# Boardd.net
KiCad netlist of a schematic drawn in EAGLE
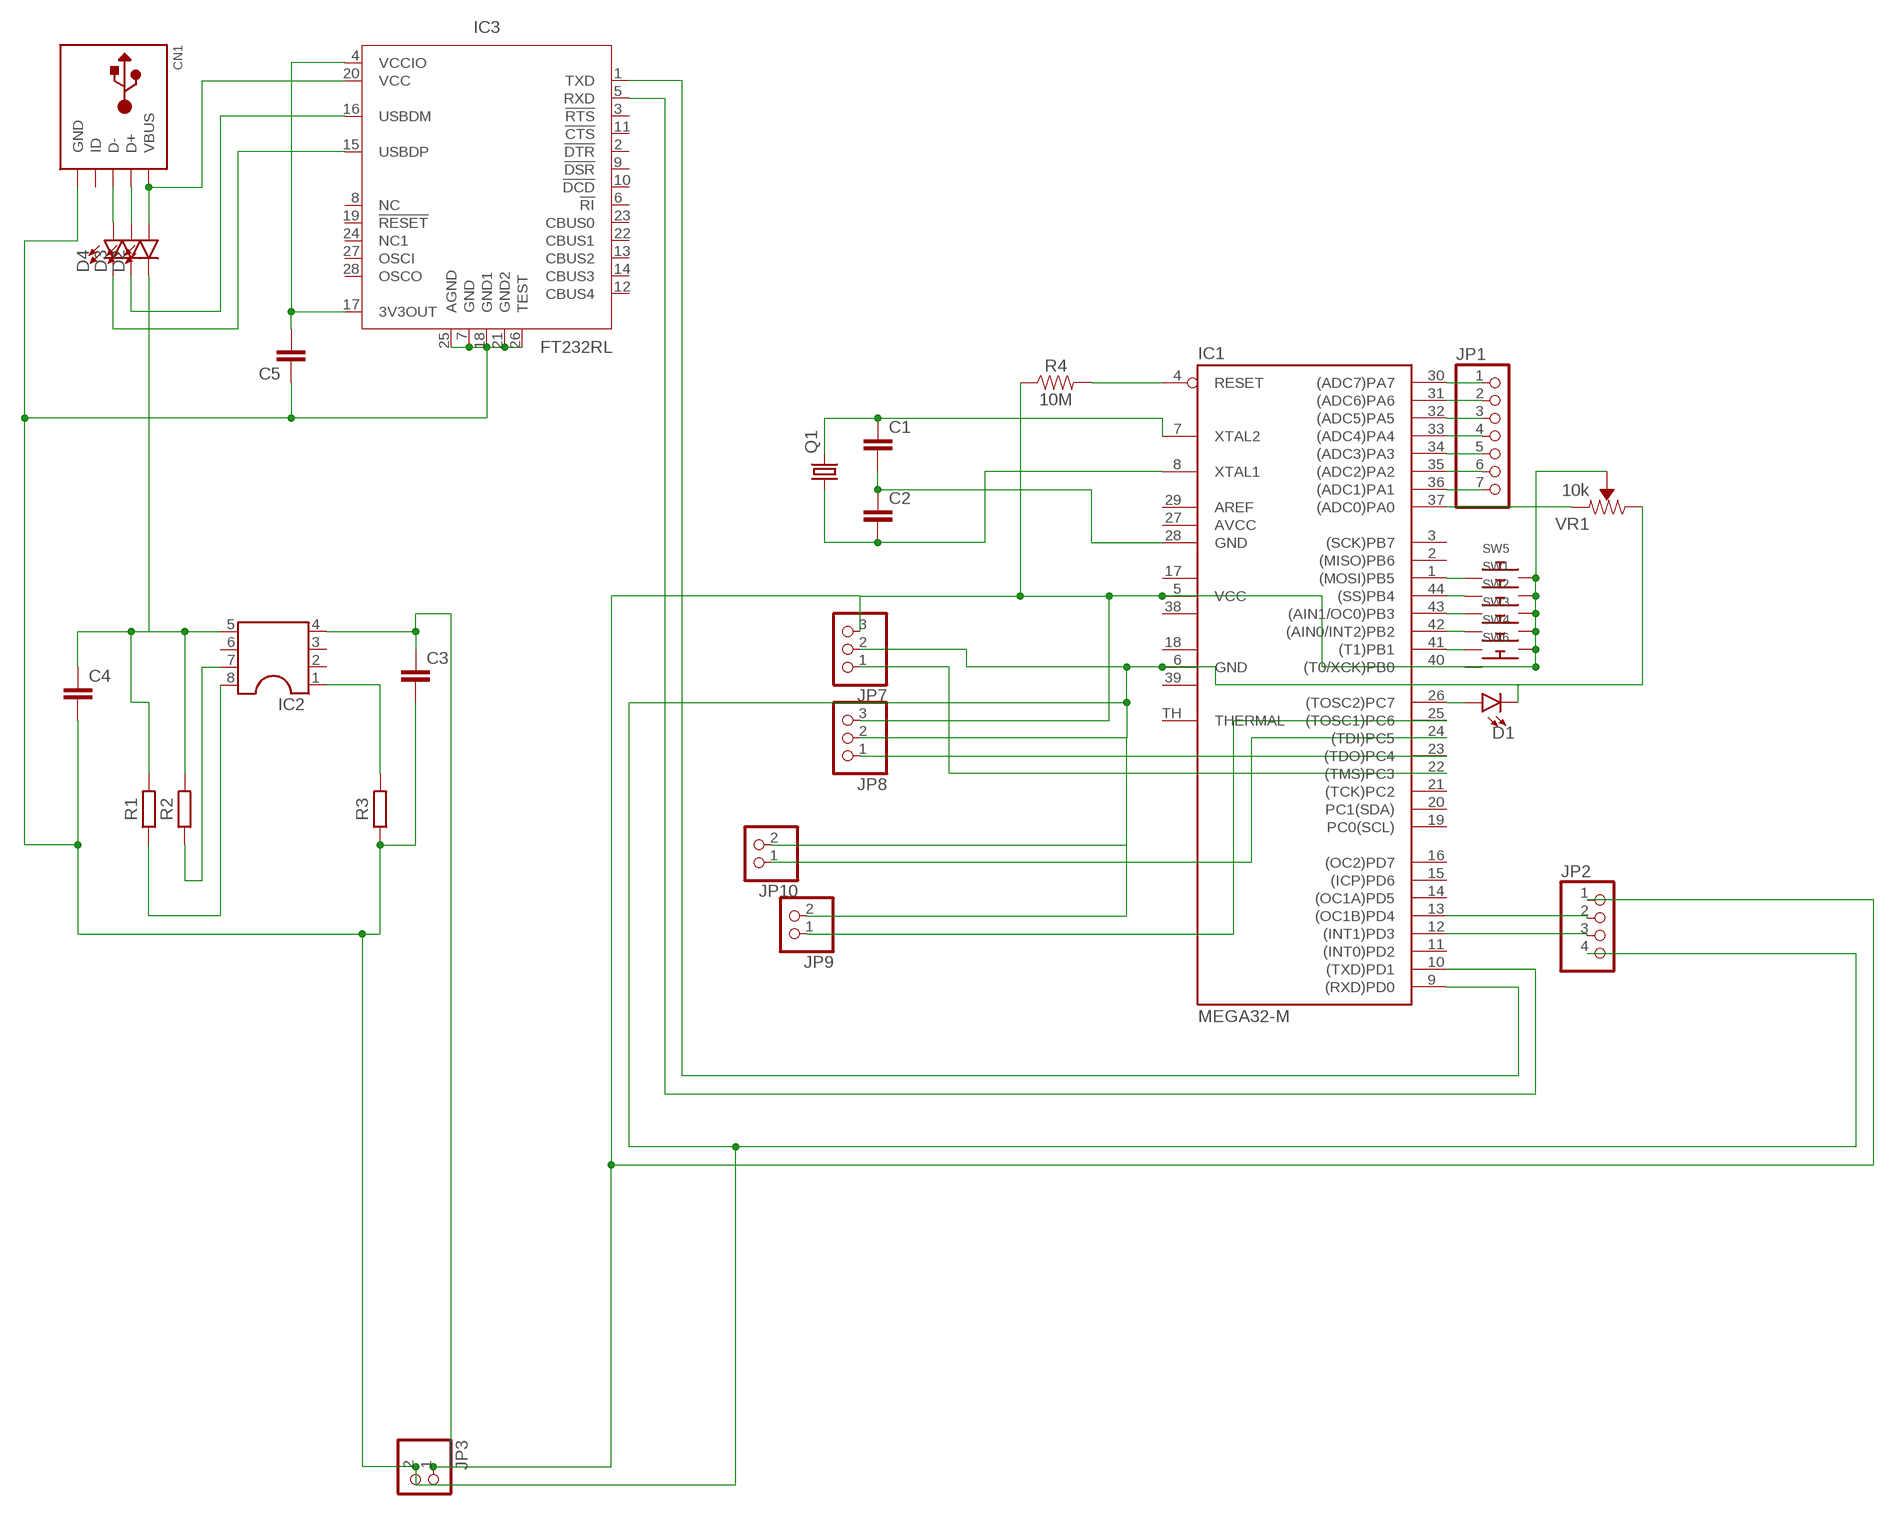
[diagram p0: schematic, sheet 1]

(export (version "E")
  (design (tool "Eeschema 10.0.6"))
  (components
    (comp (ref "C1")
      (value "C2,5-3")
      (footprint "eagle-import:C2.5-3")
      (libsource (lib "eagle-import") (part "C2,5-3"))
    )
    (comp (ref "C2")
      (value "C2,5-3")
      (footprint "eagle-import:C2.5-3")
      (libsource (lib "eagle-import") (part "C2,5-3"))
    )
    (comp (ref "C3")
      (value "C2.5/2")
      (footprint "eagle-import:C2.5-2")
      (libsource (lib "eagle-import") (part "C2.5/2"))
    )
    (comp (ref "C4")
      (value "C2.5/2")
      (footprint "eagle-import:C2.5-2")
      (libsource (lib "eagle-import") (part "C2.5/2"))
    )
    (comp (ref "C5")
      (value "C2,5-3")
      (footprint "eagle-import:C2.5-3")
      (libsource (lib "eagle-import") (part "C2,5-3"))
    )
    (comp (ref "CN1")
      (value "USBMINIB")
      (footprint "eagle-import:USB-MINIB")
      (libsource (lib "eagle-import") (part "USBMINIB"))
    )
    (comp (ref "D1")
      (value "LED0603")
      (footprint "eagle-import:LED-0603")
      (libsource (lib "eagle-import") (part "LED0603"))
    )
    (comp (ref "D2")
      (value "LED0603")
      (footprint "eagle-import:LED-0603")
      (libsource (lib "eagle-import") (part "LED0603"))
    )
    (comp (ref "D3")
      (value "LED0603")
      (footprint "eagle-import:LED-0603")
      (libsource (lib "eagle-import") (part "LED0603"))
    )
    (comp (ref "D4")
      (value "LED0603")
      (footprint "eagle-import:LED-0603")
      (libsource (lib "eagle-import") (part "LED0603"))
    )
    (comp (ref "IC1")
      (value "MEGA32-M")
      (footprint "eagle-import:MLF44-TH")
      (fields (field (name "MPN") "ATMEGA32-16MU"))
      (libsource (lib "eagle-import") (part "MEGA32-M"))
    )
    (comp (ref "IC2")
      (value "DIL8")
      (footprint "eagle-import:DIL08")
      (libsource (lib "eagle-import") (part "DIL8"))
    )
    (comp (ref "IC3")
      (value "FT232RL")
      (footprint "eagle-import:SSOP28")
      (fields (field (name "MANUFACTURER") "FTDI Chip"))
      (libsource (lib "eagle-import") (part "FT232RL_SSOP"))
    )
    (comp (ref "JP1")
      (value "PINHD-1X7")
      (footprint "eagle-import:1X07")
      (libsource (lib "eagle-import") (part "PINHD-1X7"))
    )
    (comp (ref "JP2")
      (value "PINHD-1X4")
      (footprint "eagle-import:1X04")
      (libsource (lib "eagle-import") (part "PINHD-1X4"))
    )
    (comp (ref "JP3")
      (value "PINHD-1X2")
      (footprint "eagle-import:1X02")
      (libsource (lib "eagle-import") (part "PINHD-1X2"))
    )
    (comp (ref "JP7")
      (value "PINHD-1X3")
      (footprint "eagle-import:1X03")
      (libsource (lib "eagle-import") (part "PINHD-1X3"))
    )
    (comp (ref "JP8")
      (value "PINHD-1X3")
      (footprint "eagle-import:1X03")
      (libsource (lib "eagle-import") (part "PINHD-1X3"))
    )
    (comp (ref "JP9")
      (value "PINHD-1X2")
      (footprint "eagle-import:1X02")
      (libsource (lib "eagle-import") (part "PINHD-1X2"))
    )
    (comp (ref "JP10")
      (value "PINHD-1X2")
      (footprint "eagle-import:1X02")
      (libsource (lib "eagle-import") (part "PINHD-1X2"))
    )
    (comp (ref "Q1")
      (value "CRYSTALHC49S")
      (footprint "eagle-import:HC49_S")
      (libsource (lib "eagle-import") (part "CRYSTALHC49S"))
    )
    (comp (ref "R1")
      (value "R_CHIP-0603(1608-METRIC)")
      (footprint "eagle-import:RESC1608X60")
      (libsource (lib "eagle-import") (part "RCHIP-0603(1608-METRIC)_"))
    )
    (comp (ref "R2")
      (value "R_CHIP-0603(1608-METRIC)")
      (footprint "eagle-import:RESC1608X60")
      (libsource (lib "eagle-import") (part "RCHIP-0603(1608-METRIC)_"))
    )
    (comp (ref "R3")
      (value "R_CHIP-0603(1608-METRIC)")
      (footprint "eagle-import:RESC1608X60")
      (libsource (lib "eagle-import") (part "RCHIP-0603(1608-METRIC)_"))
    )
    (comp (ref "R4")
      (value "10M")
      (footprint "eagle-import:0603")
      (libsource (lib "eagle-import") (part "10MOHM-0603-1/10W-5%"))
    )
    (comp (ref "SW1")
      (value "SWITCH_PUSHBUTTONSOFTTOUCHSMD_SJ")
      (footprint "eagle-import:PUSHBUTTON_SMD_SJ")
      (libsource (lib "eagle-import") (part "SWITCH_PUSHBUTTONSOFTTOUCHSMD_SJ"))
    )
    (comp (ref "SW2")
      (value "SWITCH_PUSHBUTTONSOFTTOUCHSMD_SJ")
      (footprint "eagle-import:PUSHBUTTON_SMD_SJ")
      (libsource (lib "eagle-import") (part "SWITCH_PUSHBUTTONSOFTTOUCHSMD_SJ"))
    )
    (comp (ref "SW3")
      (value "SWITCH_PUSHBUTTONSOFTTOUCHSMD_SJ")
      (footprint "eagle-import:PUSHBUTTON_SMD_SJ")
      (libsource (lib "eagle-import") (part "SWITCH_PUSHBUTTONSOFTTOUCHSMD_SJ"))
    )
    (comp (ref "SW4")
      (value "SWITCH_PUSHBUTTONSOFTTOUCHSMD_SJ")
      (footprint "eagle-import:PUSHBUTTON_SMD_SJ")
      (libsource (lib "eagle-import") (part "SWITCH_PUSHBUTTONSOFTTOUCHSMD_SJ"))
    )
    (comp (ref "SW5")
      (value "SWITCH_PUSHBUTTONSOFTTOUCHSMD_SJ")
      (footprint "eagle-import:PUSHBUTTON_SMD_SJ")
      (libsource (lib "eagle-import") (part "SWITCH_PUSHBUTTONSOFTTOUCHSMD_SJ"))
    )
    (comp (ref "SW6")
      (value "SWITCH_PUSHBUTTONSOFTTOUCHSMD_SJ")
      (footprint "eagle-import:PUSHBUTTON_SMD_SJ")
      (libsource (lib "eagle-import") (part "SWITCH_PUSHBUTTONSOFTTOUCHSMD_SJ"))
    )
    (comp (ref "VR1")
      (value "10k")
      (footprint "eagle-import:TRIMPOT-SMD-3MM-CLOSED")
      (libsource (lib "eagle-import") (part "TRIMPOT-SMD-3MM-CLOSED-1/8W-20%"))
    )
  )
  (nets
    (net (code "1") (name "/AVCC") (class "Default")
      (node (ref "IC1") (pin "27") (pinfunction "AVCC_27") (pintype "power_in"))
    )
    (net (code "2") (name "/GND1") (class "Default")
      (node (ref "IC1") (pin "18") (pinfunction "GND1_18") (pintype "power_in"))
    )
    (net (code "3") (name "/GND2") (class "Default")
      (node (ref "IC1") (pin "39") (pinfunction "GND2_39") (pintype "power_in"))
    )
    (net (code "4") (name "/VCC1") (class "Default")
      (node (ref "IC1") (pin "17") (pinfunction "VCC1_17") (pintype "power_in"))
    )
    (net (code "5") (name "/VCC2") (class "Default")
      (node (ref "IC1") (pin "38") (pinfunction "VCC2_38") (pintype "power_in"))
    )
    (net (code "6") (name "Net-(C1-Pad2)") (class "Default")
      (node (ref "C1") (pin "2") (pinfunction "2_2") (pintype "passive"))
      (node (ref "C2") (pin "1") (pinfunction "1_1") (pintype "passive"))
      (node (ref "IC1") (pin "28") (pinfunction "GND_28") (pintype "power_in"))
    )
    (net (code "7") (name "Net-(C4-Pad1)") (class "Default")
      (node (ref "C4") (pin "1") (pinfunction "1_1") (pintype "passive"))
      (node (ref "D2") (pin "C") (pinfunction "C_C") (pintype "passive"))
      (node (ref "IC2") (pin "5") (pinfunction "5_5") (pintype "passive"))
      (node (ref "R1") (pin "2") (pinfunction "2_2") (pintype "passive"))
      (node (ref "R2") (pin "2") (pinfunction "2_2") (pintype "passive"))
    )
    (net (code "8") (name "Net-(CN1-PadD+)") (class "Default")
      (node (ref "CN1") (pin "D+") (pinfunction "D+_D+") (pintype "bidirectional"))
      (node (ref "D3") (pin "A") (pinfunction "A_A") (pintype "passive"))
    )
    (net (code "9") (name "Net-(CN1-PadD-)") (class "Default")
      (node (ref "CN1") (pin "D-") (pinfunction "D-_D-") (pintype "bidirectional"))
      (node (ref "D4") (pin "A") (pinfunction "A_A") (pintype "passive"))
    )
    (net (code "10") (name "Net-(IC1-(ADC0)PA0)") (class "Default")
      (node (ref "IC1") (pin "37") (pinfunction "(ADC0)PA0_37") (pintype "bidirectional"))
      (node (ref "VR1") (pin "1") (pinfunction "CCW_1") (pintype "passive"))
    )
    (net (code "11") (name "Net-(IC1-(ADC1)PA1)") (class "Default")
      (node (ref "IC1") (pin "36") (pinfunction "(ADC1)PA1_36") (pintype "bidirectional"))
      (node (ref "JP1") (pin "7") (pinfunction "7_7") (pintype "passive"))
    )
    (net (code "12") (name "Net-(IC1-(ADC2)PA2)") (class "Default")
      (node (ref "IC1") (pin "35") (pinfunction "(ADC2)PA2_35") (pintype "bidirectional"))
      (node (ref "JP1") (pin "6") (pinfunction "6_6") (pintype "passive"))
    )
    (net (code "13") (name "Net-(IC1-(ADC3)PA3)") (class "Default")
      (node (ref "IC1") (pin "34") (pinfunction "(ADC3)PA3_34") (pintype "bidirectional"))
      (node (ref "JP1") (pin "5") (pinfunction "5_5") (pintype "passive"))
    )
    (net (code "14") (name "Net-(IC1-(ADC4)PA4)") (class "Default")
      (node (ref "IC1") (pin "33") (pinfunction "(ADC4)PA4_33") (pintype "bidirectional"))
      (node (ref "JP1") (pin "4") (pinfunction "4_4") (pintype "passive"))
    )
    (net (code "15") (name "Net-(IC1-(ADC5)PA5)") (class "Default")
      (node (ref "IC1") (pin "32") (pinfunction "(ADC5)PA5_32") (pintype "bidirectional"))
      (node (ref "JP1") (pin "3") (pinfunction "3_3") (pintype "passive"))
    )
    (net (code "16") (name "Net-(IC1-(ADC6)PA6)") (class "Default")
      (node (ref "IC1") (pin "31") (pinfunction "(ADC6)PA6_31") (pintype "bidirectional"))
      (node (ref "JP1") (pin "2") (pinfunction "2_2") (pintype "passive"))
    )
    (net (code "17") (name "Net-(IC1-(ADC7)PA7)") (class "Default")
      (node (ref "IC1") (pin "30") (pinfunction "(ADC7)PA7_30") (pintype "bidirectional"))
      (node (ref "JP1") (pin "1") (pinfunction "1_1") (pintype "passive"))
    )
    (net (code "18") (name "Net-(IC1-(AIN0{slash}INT2)PB2)") (class "Default")
      (node (ref "IC1") (pin "42") (pinfunction "(AIN0/INT2)PB2_42") (pintype "bidirectional"))
      (node (ref "SW3") (pin "P$1") (pinfunction "P$1_P$1") (pintype "passive"))
    )
    (net (code "19") (name "Net-(IC1-(AIN1{slash}OC0)PB3)") (class "Default")
      (node (ref "IC1") (pin "43") (pinfunction "(AIN1/OC0)PB3_43") (pintype "bidirectional"))
      (node (ref "SW2") (pin "P$1") (pinfunction "P$1_P$1") (pintype "passive"))
    )
    (net (code "20") (name "Net-(IC1-(INT1)PD3)") (class "Default")
      (node (ref "IC1") (pin "12") (pinfunction "(INT1)PD3_12") (pintype "bidirectional"))
      (node (ref "JP2") (pin "3") (pinfunction "3_3") (pintype "passive"))
    )
    (net (code "21") (name "Net-(IC1-(MOSI)PB5)") (class "Default")
      (node (ref "IC1") (pin "1") (pinfunction "(MOSI)PB5_1") (pintype "bidirectional"))
      (node (ref "SW5") (pin "P$1") (pinfunction "P$1_P$1") (pintype "passive"))
    )
    (net (code "22") (name "Net-(IC1-(OC1B)PD4)") (class "Default")
      (node (ref "IC1") (pin "13") (pinfunction "(OC1B)PD4_13") (pintype "bidirectional"))
      (node (ref "JP2") (pin "2") (pinfunction "2_2") (pintype "passive"))
    )
    (net (code "23") (name "Net-(IC1-(RXD)PD0)") (class "Default")
      (node (ref "IC1") (pin "9") (pinfunction "(RXD)PD0_9") (pintype "bidirectional"))
      (node (ref "IC3") (pin "1") (pinfunction "TXD_1") (pintype "output"))
    )
    (net (code "24") (name "Net-(IC1-(SS)PB4)") (class "Default")
      (node (ref "IC1") (pin "44") (pinfunction "(SS)PB4_44") (pintype "bidirectional"))
      (node (ref "SW1") (pin "P$1") (pinfunction "P$1_P$1") (pintype "passive"))
    )
    (net (code "25") (name "Net-(IC1-(T0{slash}XCK)PB0)") (class "Default")
      (node (ref "IC1") (pin "40") (pinfunction "(T0/XCK)PB0_40") (pintype "bidirectional"))
      (node (ref "SW6") (pin "P$1") (pinfunction "P$1_P$1") (pintype "passive"))
    )
    (net (code "26") (name "Net-(IC1-(T1)PB1)") (class "Default")
      (node (ref "IC1") (pin "41") (pinfunction "(T1)PB1_41") (pintype "bidirectional"))
      (node (ref "SW4") (pin "P$1") (pinfunction "P$1_P$1") (pintype "passive"))
    )
    (net (code "27") (name "Net-(IC1-(TDI)PC5)") (class "Default")
      (node (ref "IC1") (pin "24") (pinfunction "(TDI)PC5_24") (pintype "bidirectional"))
      (node (ref "JP10") (pin "1") (pinfunction "1_1") (pintype "passive"))
    )
    (net (code "28") (name "Net-(IC1-(TDO)PC4)") (class "Default")
      (node (ref "IC1") (pin "23") (pinfunction "(TDO)PC4_23") (pintype "bidirectional"))
      (node (ref "JP8") (pin "1") (pinfunction "1_1") (pintype "passive"))
    )
    (net (code "29") (name "Net-(IC1-(TMS)PC3)") (class "Default")
      (node (ref "IC1") (pin "22") (pinfunction "(TMS)PC3_22") (pintype "bidirectional"))
      (node (ref "JP7") (pin "1") (pinfunction "1_1") (pintype "passive"))
    )
    (net (code "30") (name "Net-(IC1-(TOSC1)PC6)") (class "Default")
      (node (ref "IC1") (pin "25") (pinfunction "(TOSC1)PC6_25") (pintype "bidirectional"))
      (node (ref "JP9") (pin "1") (pinfunction "1_1") (pintype "passive"))
    )
    (net (code "31") (name "Net-(IC1-(TOSC2)PC7)") (class "Default")
      (node (ref "D1") (pin "A") (pinfunction "A_A") (pintype "passive"))
      (node (ref "IC1") (pin "26") (pinfunction "(TOSC2)PC7_26") (pintype "bidirectional"))
    )
    (net (code "32") (name "Net-(IC1-(TXD)PD1)") (class "Default")
      (node (ref "IC1") (pin "10") (pinfunction "(TXD)PD1_10") (pintype "bidirectional"))
      (node (ref "IC3") (pin "5") (pinfunction "RXD_5") (pintype "input"))
    )
    (net (code "33") (name "Net-(IC1-RESET)") (class "Default")
      (node (ref "IC1") (pin "4") (pinfunction "RESET_4") (pintype "input"))
      (node (ref "R4") (pin "2") (pinfunction "2_2") (pintype "passive"))
    )
    (net (code "34") (name "Net-(IC1-VCC)") (class "Default")
      (node (ref "C3") (pin "1") (pinfunction "1_1") (pintype "passive"))
      (node (ref "IC1") (pin "5") (pinfunction "VCC_5") (pintype "power_in"))
      (node (ref "IC2") (pin "4") (pinfunction "4_4") (pintype "passive"))
      (node (ref "JP2") (pin "1") (pinfunction "1_1") (pintype "passive"))
      (node (ref "JP3") (pin "1") (pinfunction "1_1") (pintype "passive"))
      (node (ref "JP7") (pin "3") (pinfunction "3_3") (pintype "passive"))
      (node (ref "JP8") (pin "3") (pinfunction "3_3") (pintype "passive"))
      (node (ref "R4") (pin "1") (pinfunction "1_1") (pintype "passive"))
      (node (ref "SW1") (pin "P$2") (pinfunction "P$2_P$2") (pintype "passive"))
      (node (ref "SW2") (pin "P$2") (pinfunction "P$2_P$2") (pintype "passive"))
      (node (ref "SW3") (pin "P$2") (pinfunction "P$2_P$2") (pintype "passive"))
      (node (ref "SW4") (pin "P$2") (pinfunction "P$2_P$2") (pintype "passive"))
      (node (ref "SW5") (pin "P$2") (pinfunction "P$2_P$2") (pintype "passive"))
      (node (ref "SW6") (pin "P$2") (pinfunction "P$2_P$2") (pintype "passive"))
      (node (ref "VR1") (pin "2") (pinfunction "WIPER_2") (pintype "passive"))
    )
    (net (code "35") (name "Net-(IC1-XTAL1)") (class "Default")
      (node (ref "C2") (pin "2") (pinfunction "2_2") (pintype "passive"))
      (node (ref "IC1") (pin "8") (pinfunction "XTAL1_8") (pintype "bidirectional"))
      (node (ref "Q1") (pin "1") (pinfunction "1_1") (pintype "passive"))
    )
    (net (code "36") (name "Net-(IC1-XTAL2)") (class "Default")
      (node (ref "C1") (pin "1") (pinfunction "1_1") (pintype "passive"))
      (node (ref "IC1") (pin "7") (pinfunction "XTAL2_7") (pintype "bidirectional"))
      (node (ref "Q1") (pin "2") (pinfunction "2_2") (pintype "passive"))
    )
    (net (code "37") (name "Net-(IC2-Pad1)") (class "Default")
      (node (ref "IC2") (pin "1") (pinfunction "1_1") (pintype "passive"))
      (node (ref "R3") (pin "2") (pinfunction "2_2") (pintype "passive"))
    )
    (net (code "38") (name "Net-(IC2-Pad7)") (class "Default")
      (node (ref "IC2") (pin "7") (pinfunction "7_7") (pintype "passive"))
      (node (ref "R2") (pin "1") (pinfunction "1_1") (pintype "passive"))
    )
    (net (code "39") (name "Net-(IC2-Pad8)") (class "Default")
      (node (ref "IC2") (pin "8") (pinfunction "8_8") (pintype "passive"))
      (node (ref "R1") (pin "1") (pinfunction "1_1") (pintype "passive"))
    )
    (net (code "40") (name "Net-(IC3-3V3OUT)") (class "Default")
      (node (ref "C5") (pin "2") (pinfunction "2_2") (pintype "passive"))
      (node (ref "IC3") (pin "17") (pinfunction "3V3OUT_17") (pintype "output"))
      (node (ref "IC3") (pin "4") (pinfunction "VCCIO_4") (pintype "power_in"))
    )
    (net (code "41") (name "Net-(IC3-AGND)") (class "Default")
      (node (ref "C3") (pin "2") (pinfunction "2_2") (pintype "passive"))
      (node (ref "C4") (pin "2") (pinfunction "2_2") (pintype "passive"))
      (node (ref "C5") (pin "1") (pinfunction "1_1") (pintype "passive"))
      (node (ref "CN1") (pin "GND") (pinfunction "GND_GND") (pintype "power_in"))
      (node (ref "D1") (pin "C") (pinfunction "C_C") (pintype "passive"))
      (node (ref "IC1") (pin "6") (pinfunction "GND_6") (pintype "power_in"))
      (node (ref "IC3") (pin "18") (pinfunction "GND1_18") (pintype "power_in"))
      (node (ref "IC3") (pin "21") (pinfunction "GND2_21") (pintype "power_in"))
      (node (ref "IC3") (pin "25") (pinfunction "AGND_25") (pintype "power_in"))
      (node (ref "IC3") (pin "26") (pinfunction "TEST_26") (pintype "input"))
      (node (ref "IC3") (pin "7") (pinfunction "GND_7") (pintype "power_in"))
      (node (ref "JP10") (pin "2") (pinfunction "2_2") (pintype "passive"))
      (node (ref "JP2") (pin "4") (pinfunction "4_4") (pintype "passive"))
      (node (ref "JP3") (pin "2") (pinfunction "2_2") (pintype "passive"))
      (node (ref "JP7") (pin "2") (pinfunction "2_2") (pintype "passive"))
      (node (ref "JP8") (pin "2") (pinfunction "2_2") (pintype "passive"))
      (node (ref "JP9") (pin "2") (pinfunction "2_2") (pintype "passive"))
      (node (ref "R3") (pin "1") (pinfunction "1_1") (pintype "passive"))
      (node (ref "VR1") (pin "3") (pinfunction "CW_3") (pintype "passive"))
    )
    (net (code "42") (name "Net-(IC3-USBDM)") (class "Default")
      (node (ref "D3") (pin "C") (pinfunction "C_C") (pintype "passive"))
      (node (ref "IC3") (pin "16") (pinfunction "USBDM_16") (pintype "bidirectional"))
    )
    (net (code "43") (name "Net-(IC3-USBDP)") (class "Default")
      (node (ref "D4") (pin "C") (pinfunction "C_C") (pintype "passive"))
      (node (ref "IC3") (pin "15") (pinfunction "USBDP_15") (pintype "bidirectional"))
    )
    (net (code "44") (name "Net-(IC3-VCC)") (class "Default")
      (node (ref "CN1") (pin "VBUS") (pinfunction "VBUS_VBUS") (pintype "power_in"))
      (node (ref "D2") (pin "A") (pinfunction "A_A") (pintype "passive"))
      (node (ref "IC3") (pin "20") (pinfunction "VCC_20") (pintype "power_in"))
    )
    (net (code "45") (name "unconnected-(CN1-PadID)") (class "Default")
      (node (ref "CN1") (pin "ID") (pinfunction "ID_ID") (pintype "bidirectional"))
    )
    (net (code "46") (name "unconnected-(IC1-(ICP)PD6-Pad15)") (class "Default")
      (node (ref "IC1") (pin "15") (pinfunction "(ICP)PD6_15") (pintype "bidirectional"))
    )
    (net (code "47") (name "unconnected-(IC1-(INT0)PD2-Pad11)") (class "Default")
      (node (ref "IC1") (pin "11") (pinfunction "(INT0)PD2_11") (pintype "bidirectional"))
    )
    (net (code "48") (name "unconnected-(IC1-(MISO)PB6-Pad2)") (class "Default")
      (node (ref "IC1") (pin "2") (pinfunction "(MISO)PB6_2") (pintype "bidirectional"))
    )
    (net (code "49") (name "unconnected-(IC1-(OC1A)PD5-Pad14)") (class "Default")
      (node (ref "IC1") (pin "14") (pinfunction "(OC1A)PD5_14") (pintype "bidirectional"))
    )
    (net (code "50") (name "unconnected-(IC1-(OC2)PD7-Pad16)") (class "Default")
      (node (ref "IC1") (pin "16") (pinfunction "(OC2)PD7_16") (pintype "bidirectional"))
    )
    (net (code "51") (name "unconnected-(IC1-(SCK)PB7-Pad3)") (class "Default")
      (node (ref "IC1") (pin "3") (pinfunction "(SCK)PB7_3") (pintype "bidirectional"))
    )
    (net (code "52") (name "unconnected-(IC1-(TCK)PC2-Pad21)") (class "Default")
      (node (ref "IC1") (pin "21") (pinfunction "(TCK)PC2_21") (pintype "bidirectional"))
    )
    (net (code "53") (name "unconnected-(IC1-AREF-Pad29)") (class "Default")
      (node (ref "IC1") (pin "29") (pinfunction "AREF_29") (pintype "passive"))
    )
    (net (code "54") (name "unconnected-(IC1-PC0(SCL)-Pad19)") (class "Default")
      (node (ref "IC1") (pin "19") (pinfunction "PC0(SCL)_19") (pintype "bidirectional"))
    )
    (net (code "55") (name "unconnected-(IC1-PC1(SDA)-Pad20)") (class "Default")
      (node (ref "IC1") (pin "20") (pinfunction "PC1(SDA)_20") (pintype "bidirectional"))
    )
    (net (code "56") (name "unconnected-(IC1-THERMAL-PadTH)") (class "Default")
      (node (ref "IC1") (pin "TH") (pinfunction "THERMAL_TH") (pintype "input"))
    )
    (net (code "57") (name "unconnected-(IC2-Pad2)") (class "Default")
      (node (ref "IC2") (pin "2") (pinfunction "2_2") (pintype "passive"))
    )
    (net (code "58") (name "unconnected-(IC2-Pad3)") (class "Default")
      (node (ref "IC2") (pin "3") (pinfunction "3_3") (pintype "passive"))
    )
    (net (code "59") (name "unconnected-(IC2-Pad6)") (class "Default")
      (node (ref "IC2") (pin "6") (pinfunction "6_6") (pintype "passive"))
    )
    (net (code "60") (name "unconnected-(IC3-CBUS0-Pad23)") (class "Default")
      (node (ref "IC3") (pin "23") (pinfunction "CBUS0_23") (pintype "bidirectional"))
    )
    (net (code "61") (name "unconnected-(IC3-CBUS1-Pad22)") (class "Default")
      (node (ref "IC3") (pin "22") (pinfunction "CBUS1_22") (pintype "bidirectional"))
    )
    (net (code "62") (name "unconnected-(IC3-CBUS2-Pad13)") (class "Default")
      (node (ref "IC3") (pin "13") (pinfunction "CBUS2_13") (pintype "bidirectional"))
    )
    (net (code "63") (name "unconnected-(IC3-CBUS3-Pad14)") (class "Default")
      (node (ref "IC3") (pin "14") (pinfunction "CBUS3_14") (pintype "bidirectional"))
    )
    (net (code "64") (name "unconnected-(IC3-CBUS4-Pad12)") (class "Default")
      (node (ref "IC3") (pin "12") (pinfunction "CBUS4_12") (pintype "bidirectional"))
    )
    (net (code "65") (name "unconnected-(IC3-NC-Pad8)") (class "Default")
      (node (ref "IC3") (pin "8") (pinfunction "NC_8") (pintype "no_connect"))
    )
    (net (code "66") (name "unconnected-(IC3-NC1-Pad24)") (class "Default")
      (node (ref "IC3") (pin "24") (pinfunction "NC1_24") (pintype "no_connect"))
    )
    (net (code "67") (name "unconnected-(IC3-OSCI-Pad27)") (class "Default")
      (node (ref "IC3") (pin "27") (pinfunction "OSCI_27") (pintype "input"))
    )
    (net (code "68") (name "unconnected-(IC3-OSCO-Pad28)") (class "Default")
      (node (ref "IC3") (pin "28") (pinfunction "OSCO_28") (pintype "input"))
    )
    (net (code "69") (name "unconnected-(IC3-~{CTS}-Pad11)") (class "Default")
      (node (ref "IC3") (pin "11") (pinfunction "~{CTS}_11") (pintype "input"))
    )
    (net (code "70") (name "unconnected-(IC3-~{DCD}-Pad10)") (class "Default")
      (node (ref "IC3") (pin "10") (pinfunction "~{DCD}_10") (pintype "input"))
    )
    (net (code "71") (name "unconnected-(IC3-~{DSR}-Pad9)") (class "Default")
      (node (ref "IC3") (pin "9") (pinfunction "~{DSR}_9") (pintype "input"))
    )
    (net (code "72") (name "unconnected-(IC3-~{DTR}-Pad2)") (class "Default")
      (node (ref "IC3") (pin "2") (pinfunction "~{DTR}_2") (pintype "output"))
    )
    (net (code "73") (name "unconnected-(IC3-~{RESET}-Pad19)") (class "Default")
      (node (ref "IC3") (pin "19") (pinfunction "~{RESET}_19") (pintype "input"))
    )
    (net (code "74") (name "unconnected-(IC3-~{RI}-Pad6)") (class "Default")
      (node (ref "IC3") (pin "6") (pinfunction "~{RI}_6") (pintype "input"))
    )
    (net (code "75") (name "unconnected-(IC3-~{RTS}-Pad3)") (class "Default")
      (node (ref "IC3") (pin "3") (pinfunction "~{RTS}_3") (pintype "output"))
    )
  )
)
